# I2C.net
KiCad netlist of a schematic drawn in Altium Designer
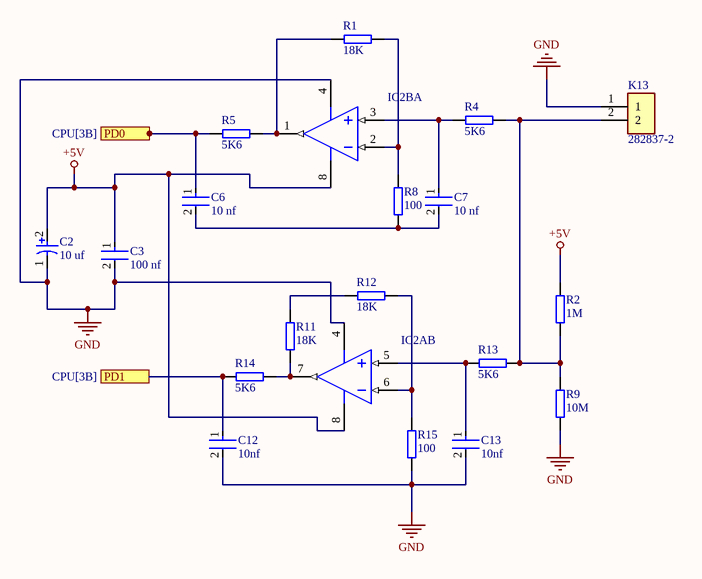
[diagram p0: I2C.SchDoc]

(export (version "E")
  (design (tool "Eeschema 10.0.6"))
  (components
    (comp (ref "C2")
      (value "10 uf")
      (footprint "CE_D8_L10")
      (fields (field (name "MANUFACTURER") "Panasonic"))
      (libsource (lib "Soldeerstation_Final") (part "Capacitor_Electrolytic"))
    )
    (comp (ref "C3")
      (value "100 nf")
      (footprint "CC_0805_L")
      (fields
        (field (name "MANUFACTURER") "KEMET")
        (field (name "OCTOPART") "https://octopart.com/c0805c224k5ractu-kemet-144670")
        (field (name "MANUFACTURER PART NUMBER") "C0805C224K5RACTU")
      )
      (libsource (lib "Soldeerstation_Final") (part "Capacitor_Ceramic"))
    )
    (comp (ref "C6")
      (value "10 nf")
      (footprint "CC_0805_L")
      (fields
        (field (name "MANUFACTURER") "KEMET")
        (field (name "OCTOPART") "https://octopart.com/c0805c224k5ractu-kemet-144670")
        (field (name "MANUFACTURER PART NUMBER") "C0805C224K5RACTU")
      )
      (libsource (lib "Soldeerstation_Final") (part "Capacitor_Ceramic"))
    )
    (comp (ref "C7")
      (value "10 nf")
      (footprint "CC_0805_L")
      (fields
        (field (name "MANUFACTURER") "KEMET")
        (field (name "OCTOPART") "https://octopart.com/c0805c224k5ractu-kemet-144670")
        (field (name "MANUFACTURER PART NUMBER") "C0805C224K5RACTU")
      )
      (libsource (lib "Soldeerstation_Final") (part "Capacitor_Ceramic"))
    )
    (comp (ref "C12")
      (value "10nf")
      (footprint "CC_0805_L")
      (fields
        (field (name "MANUFACTURER") "KEMET")
        (field (name "OCTOPART") "https://octopart.com/c0805c224k5ractu-kemet-144670")
        (field (name "MANUFACTURER PART NUMBER") "C0805C224K5RACTU")
      )
      (libsource (lib "Soldeerstation_Final") (part "Capacitor_Ceramic"))
    )
    (comp (ref "C13")
      (value "10nf")
      (footprint "CC_0805_L")
      (fields
        (field (name "MANUFACTURER") "KEMET")
        (field (name "OCTOPART") "https://octopart.com/c0805c224k5ractu-kemet-144670")
        (field (name "MANUFACTURER PART NUMBER") "C0805C224K5RACTU")
      )
      (libsource (lib "Soldeerstation_Final") (part "Capacitor_Ceramic"))
    )
    (comp (ref "IC2A")
      (value "~")
      (footprint "MSOP_8_M")
      (libsource (lib "Soldeerstation_Final") (part "Dual_Opamp"))
    )
    (comp (ref "IC2B")
      (value "~")
      (footprint "MSOP_8_M")
      (libsource (lib "Soldeerstation_Final") (part "Dual_Opamp"))
    )
    (comp (ref "K13")
      (value "282837-2")
      (footprint "TE_282837-2")
      (fields (field (name "MF") "TE Connectivity"))
      (libsource (lib "282837-2") (part "282837-2"))
    )
    (comp (ref "R1")
      (value "18K")
      (footprint "CC_0805_m")
      (fields (field (name "MANUFACTURER") "Vishay Dale") (field (name "PART NUMBER") "CRCW08050000Z0EA"))
      (libsource (lib "Soldeerstation_Final") (part "Resistor"))
    )
    (comp (ref "R2")
      (value "1M")
      (footprint "CC_0805_m")
      (fields (field (name "MANUFACTURER") "Vishay Dale") (field (name "PART NUMBER") "CRCW08050000Z0EA"))
      (libsource (lib "Soldeerstation_Final") (part "Resistor"))
    )
    (comp (ref "R4")
      (value "5K6")
      (footprint "CC_0805_m")
      (fields (field (name "MANUFACTURER") "Vishay Dale") (field (name "PART NUMBER") "CRCW08050000Z0EA"))
      (libsource (lib "Soldeerstation_Final") (part "Resistor"))
    )
    (comp (ref "R5")
      (value "5K6")
      (footprint "CC_0805_m")
      (fields (field (name "MANUFACTURER") "Vishay Dale") (field (name "PART NUMBER") "CRCW08050000Z0EA"))
      (libsource (lib "Soldeerstation_Final") (part "Resistor"))
    )
    (comp (ref "R8")
      (value "100")
      (footprint "CC_0805_m")
      (fields (field (name "MANUFACTURER") "Vishay Dale") (field (name "PART NUMBER") "CRCW08050000Z0EA"))
      (libsource (lib "Soldeerstation_Final") (part "Resistor"))
    )
    (comp (ref "R9")
      (value "10M")
      (footprint "CC_0805_m")
      (fields (field (name "MANUFACTURER") "Vishay Dale") (field (name "PART NUMBER") "CRCW08050000Z0EA"))
      (libsource (lib "Soldeerstation_Final") (part "Resistor"))
    )
    (comp (ref "R11")
      (value "18K")
      (footprint "CC_0805_m")
      (fields (field (name "MANUFACTURER") "Vishay Dale") (field (name "PART NUMBER") "CRCW08050000Z0EA"))
      (libsource (lib "Soldeerstation_Final") (part "Resistor"))
    )
    (comp (ref "R12")
      (value "18K")
      (footprint "CC_0805_m")
      (fields (field (name "MANUFACTURER") "Vishay Dale") (field (name "PART NUMBER") "CRCW08050000Z0EA"))
      (libsource (lib "Soldeerstation_Final") (part "Resistor"))
    )
    (comp (ref "R13")
      (value "5K6")
      (footprint "CC_0805_m")
      (fields (field (name "MANUFACTURER") "Vishay Dale") (field (name "PART NUMBER") "CRCW08050000Z0EA"))
      (libsource (lib "Soldeerstation_Final") (part "Resistor"))
    )
    (comp (ref "R14")
      (value "5K6")
      (footprint "CC_0805_m")
      (fields (field (name "MANUFACTURER") "Vishay Dale") (field (name "PART NUMBER") "CRCW08050000Z0EA"))
      (libsource (lib "Soldeerstation_Final") (part "Resistor"))
    )
    (comp (ref "R15")
      (value "100")
      (footprint "CC_0805_m")
      (fields (field (name "MANUFACTURER") "Vishay Dale") (field (name "PART NUMBER") "CRCW08050000Z0EA"))
      (libsource (lib "Soldeerstation_Final") (part "Resistor"))
    )
  )
  (nets
    (net (code "1") (name "+5V") (class "Default")
      (node (ref "C2") (pin "2") (pinfunction "2_2") (pintype "passive"))
      (node (ref "C3") (pin "1") (pinfunction "1_1") (pintype "passive"))
      (node (ref "IC2A") (pin "8") (pinfunction "VDD_8") (pintype "power_in"))
      (node (ref "IC2B") (pin "8") (pinfunction "VDD_8") (pintype "power_in"))
      (node (ref "R2") (pin "2") (pinfunction "2_2") (pintype "passive"))
    )
    (net (code "2") (name "/PD0") (class "Default")
      (node (ref "C6") (pin "1") (pinfunction "1_1") (pintype "passive"))
      (node (ref "R5") (pin "1") (pinfunction "1_1") (pintype "passive"))
    )
    (net (code "3") (name "/PD1") (class "Default")
      (node (ref "C12") (pin "1") (pinfunction "1_1") (pintype "passive"))
      (node (ref "R14") (pin "1") (pinfunction "1_1") (pintype "passive"))
    )
    (net (code "4") (name "GND") (class "Default")
      (node (ref "C12") (pin "2") (pinfunction "2_2") (pintype "passive"))
      (node (ref "C13") (pin "2") (pinfunction "2_2") (pintype "passive"))
      (node (ref "C2") (pin "1") (pinfunction "1_1") (pintype "passive"))
      (node (ref "C3") (pin "2") (pinfunction "2_2") (pintype "passive"))
      (node (ref "IC2A") (pin "4") (pinfunction "VSS_4") (pintype "power_in"))
      (node (ref "IC2B") (pin "4") (pinfunction "VSS_4") (pintype "power_in"))
      (node (ref "K13") (pin "1") (pinfunction "1_1") (pintype "passive"))
      (node (ref "R15") (pin "1") (pinfunction "1_1") (pintype "passive"))
      (node (ref "R9") (pin "1") (pinfunction "1_1") (pintype "passive"))
    )
    (net (code "5") (name "Net-(C6-Pad2)") (class "Default")
      (node (ref "C6") (pin "2") (pinfunction "2_2") (pintype "passive"))
      (node (ref "C7") (pin "2") (pinfunction "2_2") (pintype "passive"))
      (node (ref "R8") (pin "1") (pinfunction "1_1") (pintype "passive"))
    )
    (net (code "6") (name "Net-(IC2AB-VINB+)") (class "Default")
      (node (ref "C13") (pin "1") (pinfunction "1_1") (pintype "passive"))
      (node (ref "IC2A") (pin "5") (pinfunction "VINB+_5") (pintype "input"))
      (node (ref "R13") (pin "1") (pinfunction "1_1") (pintype "passive"))
    )
    (net (code "7") (name "Net-(IC2AB-VINB-)") (class "Default")
      (node (ref "IC2A") (pin "6") (pinfunction "VINB-_6") (pintype "input"))
      (node (ref "R12") (pin "2") (pinfunction "2_2") (pintype "passive"))
      (node (ref "R15") (pin "2") (pinfunction "2_2") (pintype "passive"))
    )
    (net (code "8") (name "Net-(IC2AB-VOUTB)") (class "Default")
      (node (ref "IC2A") (pin "7") (pinfunction "VOUTB_7") (pintype "output"))
      (node (ref "R11") (pin "1") (pinfunction "1_1") (pintype "passive"))
      (node (ref "R14") (pin "2") (pinfunction "2_2") (pintype "passive"))
    )
    (net (code "9") (name "Net-(IC2BA-VINA+)") (class "Default")
      (node (ref "C7") (pin "1") (pinfunction "1_1") (pintype "passive"))
      (node (ref "IC2B") (pin "3") (pinfunction "VINA+_3") (pintype "input"))
      (node (ref "R4") (pin "1") (pinfunction "1_1") (pintype "passive"))
    )
    (net (code "10") (name "Net-(IC2BA-VINA-)") (class "Default")
      (node (ref "IC2B") (pin "2") (pinfunction "VINA-_2") (pintype "input"))
      (node (ref "R1") (pin "2") (pinfunction "2_2") (pintype "passive"))
      (node (ref "R8") (pin "2") (pinfunction "2_2") (pintype "passive"))
    )
    (net (code "11") (name "Net-(IC2BA-VOUTA)") (class "Default")
      (node (ref "IC2B") (pin "1") (pinfunction "VOUTA_1") (pintype "output"))
      (node (ref "R1") (pin "1") (pinfunction "1_1") (pintype "passive"))
      (node (ref "R5") (pin "2") (pinfunction "2_2") (pintype "passive"))
    )
    (net (code "12") (name "Net-(K13-Pad2)") (class "Default")
      (node (ref "K13") (pin "2") (pinfunction "2_2") (pintype "passive"))
      (node (ref "R13") (pin "2") (pinfunction "2_2") (pintype "passive"))
      (node (ref "R2") (pin "1") (pinfunction "1_1") (pintype "passive"))
      (node (ref "R4") (pin "2") (pinfunction "2_2") (pintype "passive"))
      (node (ref "R9") (pin "2") (pinfunction "2_2") (pintype "passive"))
    )
    (net (code "13") (name "Net-(R11-Pad2)") (class "Default")
      (node (ref "R11") (pin "2") (pinfunction "2_2") (pintype "passive"))
      (node (ref "R12") (pin "1") (pinfunction "1_1") (pintype "passive"))
    )
  )
)
